# Core48.net
KiCad netlist of a schematic drawn in Altium Designer
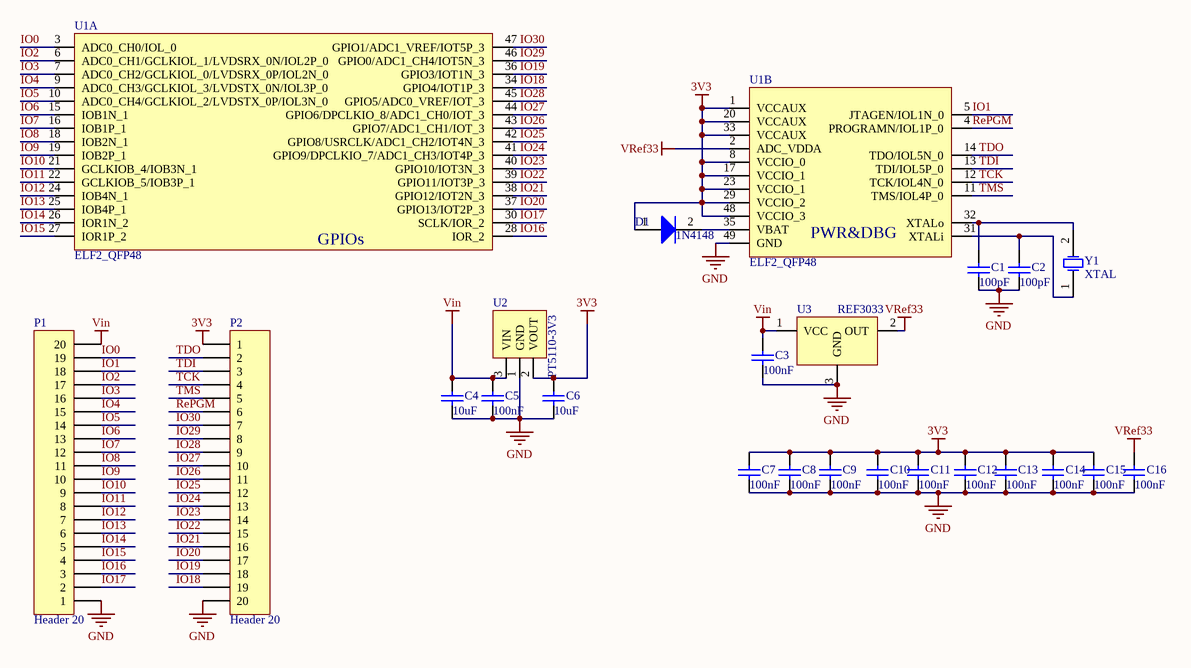
[diagram p0: Core48.SchDoc]

(export (version "E")
  (design (tool "Eeschema 10.0.6"))
  (components
    (comp (ref "C1")
      (value "100pF")
      (footprint "0603C")
      (description "Capacitor")
      (fields (field (name "Comment") "Cap") (field (name "PUBLISHER") "Altium Limited"))
      (libsource (lib "Miscellaneous Devices") (part "Cap"))
    )
    (comp (ref "C2")
      (value "100pF")
      (footprint "0603C")
      (description "Capacitor")
      (fields (field (name "Comment") "Cap") (field (name "PUBLISHER") "Altium Limited"))
      (libsource (lib "Miscellaneous Devices") (part "Cap"))
    )
    (comp (ref "C3")
      (value "100nF")
      (footprint "0603C")
      (description "Capacitor")
      (fields (field (name "Comment") "Cap") (field (name "PUBLISHER") "Altium Limited"))
      (libsource (lib "Miscellaneous Devices") (part "Cap"))
    )
    (comp (ref "C4")
      (value "10uF")
      (footprint "0603C")
      (description "Capacitor")
      (fields (field (name "Comment") "Cap") (field (name "PUBLISHER") "Altium Limited"))
      (libsource (lib "Miscellaneous Devices") (part "Cap"))
    )
    (comp (ref "C5")
      (value "100nF")
      (footprint "0603C")
      (description "Capacitor")
      (fields (field (name "Comment") "Cap") (field (name "PUBLISHER") "Altium Limited"))
      (libsource (lib "Miscellaneous Devices") (part "Cap"))
    )
    (comp (ref "C6")
      (value "10uF")
      (footprint "0603C")
      (description "Capacitor")
      (fields (field (name "Comment") "Cap") (field (name "PUBLISHER") "Altium Limited"))
      (libsource (lib "Miscellaneous Devices") (part "Cap"))
    )
    (comp (ref "C7")
      (value "100nF")
      (footprint "0603C")
      (description "Capacitor")
      (fields (field (name "Comment") "Cap") (field (name "PUBLISHER") "Altium Limited"))
      (libsource (lib "Miscellaneous Devices") (part "Cap"))
    )
    (comp (ref "C8")
      (value "100nF")
      (footprint "0603C")
      (description "Capacitor")
      (fields (field (name "Comment") "Cap") (field (name "PUBLISHER") "Altium Limited"))
      (libsource (lib "Miscellaneous Devices") (part "Cap"))
    )
    (comp (ref "C9")
      (value "100nF")
      (footprint "0603C")
      (description "Capacitor")
      (fields (field (name "Comment") "Cap") (field (name "PUBLISHER") "Altium Limited"))
      (libsource (lib "Miscellaneous Devices") (part "Cap"))
    )
    (comp (ref "C10")
      (value "100nF")
      (footprint "0603C")
      (description "Capacitor")
      (fields (field (name "Comment") "Cap") (field (name "PUBLISHER") "Altium Limited"))
      (libsource (lib "Miscellaneous Devices") (part "Cap"))
    )
    (comp (ref "C11")
      (value "100nF")
      (footprint "0603C")
      (description "Capacitor")
      (fields (field (name "Comment") "Cap") (field (name "PUBLISHER") "Altium Limited"))
      (libsource (lib "Miscellaneous Devices") (part "Cap"))
    )
    (comp (ref "C12")
      (value "100nF")
      (footprint "0603C")
      (description "Capacitor")
      (fields (field (name "Comment") "Cap") (field (name "PUBLISHER") "Altium Limited"))
      (libsource (lib "Miscellaneous Devices") (part "Cap"))
    )
    (comp (ref "C13")
      (value "100nF")
      (footprint "0603C")
      (description "Capacitor")
      (fields (field (name "Comment") "Cap") (field (name "PUBLISHER") "Altium Limited"))
      (libsource (lib "Miscellaneous Devices") (part "Cap"))
    )
    (comp (ref "C14")
      (value "100nF")
      (footprint "0603C")
      (description "Capacitor")
      (fields (field (name "Comment") "Cap") (field (name "PUBLISHER") "Altium Limited"))
      (libsource (lib "Miscellaneous Devices") (part "Cap"))
    )
    (comp (ref "C15")
      (value "100nF")
      (footprint "0603C")
      (description "Capacitor")
      (fields (field (name "Comment") "Cap") (field (name "PUBLISHER") "Altium Limited"))
      (libsource (lib "Miscellaneous Devices") (part "Cap"))
    )
    (comp (ref "C16")
      (value "100nF")
      (footprint "0603C")
      (description "Capacitor")
      (fields (field (name "Comment") "Cap") (field (name "PUBLISHER") "Altium Limited"))
      (libsource (lib "Miscellaneous Devices") (part "Cap"))
    )
    (comp (ref "D1")
      (value "1N4148")
      (footprint "6-0805_Diode")
      (description "Default Diode")
      (fields (field (name "PUBLISHER") "Altium Limited"))
      (libsource (lib "Miscellaneous Devices") (part "Diode"))
    )
    (comp (ref "P1")
      (value "Header 20")
      (footprint "HDR1X20")
      (description "Header, 20-Pin")
      (fields (field (name "PUBLISHER") "Altium Limited"))
      (libsource (lib "Miscellaneous Connectors") (part "Header 20"))
    )
    (comp (ref "P2")
      (value "Header 20")
      (footprint "HDR1X20")
      (description "Header, 20-Pin")
      (fields (field (name "PUBLISHER") "Altium Limited"))
      (libsource (lib "") (part "Header 20_1"))
    )
    (comp (ref "U1")
      (value "ELF2_QFP48")
      (footprint "TSQFP48-7*7")
      (libsource (lib "AnLogic_FPGAs") (part "ELF2_QFP48"))
    )
    (comp (ref "U2")
      (value "PT5110-3V3")
      (footprint "SOT-89-3")
      (libsource (lib "PowerChips") (part "PT5110"))
    )
    (comp (ref "U3") (value "REF3033") (footprint "SOT23") (libsource (lib "PublicSch") (part "REF30xx")))
    (comp (ref "Y1")
      (value "XTAL")
      (footprint "XTAL-5032")
      (description "Crystal Oscillator")
      (fields (field (name "PUBLISHER") "Altium Limited"))
      (libsource (lib "Miscellaneous Devices") (part "XTAL"))
    )
  )
  (nets
    (net (code "1") (name "/IO0") (class "Default")
      (node (ref "P1") (pin "19") (pinfunction "19_19") (pintype "passive"))
      (node (ref "U1") (pin "3") (pinfunction "ADC0_CH0/IOL_0_3") (pintype "power_in"))
    )
    (net (code "2") (name "/IO1") (class "Default")
      (node (ref "P1") (pin "18") (pinfunction "18_18") (pintype "passive"))
      (node (ref "U1") (pin "5") (pinfunction "JTAGEN/IOL1N_0_5") (pintype "power_in"))
    )
    (net (code "3") (name "/IO2") (class "Default")
      (node (ref "P1") (pin "17") (pinfunction "17_17") (pintype "passive"))
      (node (ref "U1") (pin "6") (pinfunction "ADC0_CH1/GCLKIOL_1/LVDSRX_0N/IOL2P_0_6") (pintype "power_in"))
    )
    (net (code "4") (name "/IO3") (class "Default")
      (node (ref "P1") (pin "16") (pinfunction "16_16") (pintype "passive"))
      (node (ref "U1") (pin "7") (pinfunction "ADC0_CH2/GCLKIOL_0/LVDSRX_0P/IOL2N_0_7") (pintype "power_in"))
    )
    (net (code "5") (name "/IO4") (class "Default")
      (node (ref "P1") (pin "15") (pinfunction "15_15") (pintype "passive"))
      (node (ref "U1") (pin "9") (pinfunction "ADC0_CH3/GCLKIOL_3/LVDSTX_0N/IOL3P_0_9") (pintype "power_in"))
    )
    (net (code "6") (name "/IO5") (class "Default")
      (node (ref "P1") (pin "14") (pinfunction "14_14") (pintype "passive"))
      (node (ref "U1") (pin "10") (pinfunction "ADC0_CH4/GCLKIOL_2/LVDSTX_0P/IOL3N_0_10") (pintype "power_in"))
    )
    (net (code "7") (name "/IO6") (class "Default")
      (node (ref "P1") (pin "13") (pinfunction "13_13") (pintype "passive"))
      (node (ref "U1") (pin "15") (pinfunction "IOB1N_1_15") (pintype "power_in"))
    )
    (net (code "8") (name "/IO7") (class "Default")
      (node (ref "P1") (pin "12") (pinfunction "12_12") (pintype "passive"))
      (node (ref "U1") (pin "16") (pinfunction "IOB1P_1_16") (pintype "power_in"))
    )
    (net (code "9") (name "/IO8") (class "Default")
      (node (ref "P1") (pin "11") (pinfunction "11_11") (pintype "passive"))
      (node (ref "U1") (pin "18") (pinfunction "IOB2N_1_18") (pintype "power_in"))
    )
    (net (code "10") (name "/IO9") (class "Default")
      (node (ref "P1") (pin "10") (pinfunction "10_10") (pintype "passive"))
      (node (ref "U1") (pin "19") (pinfunction "IOB2P_1_19") (pintype "power_in"))
    )
    (net (code "11") (name "/IO10") (class "Default")
      (node (ref "P1") (pin "9") (pinfunction "9_9") (pintype "passive"))
      (node (ref "U1") (pin "21") (pinfunction "GCLKIOB_4/IOB3N_1_21") (pintype "power_in"))
    )
    (net (code "12") (name "/IO11") (class "Default")
      (node (ref "P1") (pin "8") (pinfunction "8_8") (pintype "passive"))
      (node (ref "U1") (pin "22") (pinfunction "GCLKIOB_5/IOB3P_1_22") (pintype "power_in"))
    )
    (net (code "13") (name "/IO12") (class "Default")
      (node (ref "P1") (pin "7") (pinfunction "7_7") (pintype "passive"))
      (node (ref "U1") (pin "24") (pinfunction "IOB4N_1_24") (pintype "power_in"))
    )
    (net (code "14") (name "/IO13") (class "Default")
      (node (ref "P1") (pin "6") (pinfunction "6_6") (pintype "passive"))
      (node (ref "U1") (pin "25") (pinfunction "IOB4P_1_25") (pintype "power_in"))
    )
    (net (code "15") (name "/IO14") (class "Default")
      (node (ref "P1") (pin "5") (pinfunction "5_5") (pintype "passive"))
      (node (ref "U1") (pin "26") (pinfunction "IOR1N_2_26") (pintype "power_in"))
    )
    (net (code "16") (name "/IO15") (class "Default")
      (node (ref "P1") (pin "4") (pinfunction "4_4") (pintype "passive"))
      (node (ref "U1") (pin "27") (pinfunction "IOR1P_2_27") (pintype "power_in"))
    )
    (net (code "17") (name "/IO16") (class "Default")
      (node (ref "P1") (pin "3") (pinfunction "3_3") (pintype "passive"))
      (node (ref "U1") (pin "28") (pinfunction "IOR_2_28") (pintype "power_in"))
    )
    (net (code "18") (name "/IO17") (class "Default")
      (node (ref "P1") (pin "2") (pinfunction "2_2") (pintype "passive"))
      (node (ref "U1") (pin "30") (pinfunction "SCLK/IOR_2_30") (pintype "power_in"))
    )
    (net (code "19") (name "/IO18") (class "Default")
      (node (ref "P2") (pin "19") (pinfunction "19_19") (pintype "passive"))
      (node (ref "U1") (pin "34") (pinfunction "GPIO4/IOT1P_3_34") (pintype "power_in"))
    )
    (net (code "20") (name "/IO19") (class "Default")
      (node (ref "P2") (pin "18") (pinfunction "18_18") (pintype "passive"))
      (node (ref "U1") (pin "36") (pinfunction "GPIO3/IOT1N_3_36") (pintype "power_in"))
    )
    (net (code "21") (name "/IO20") (class "Default")
      (node (ref "P2") (pin "17") (pinfunction "17_17") (pintype "passive"))
      (node (ref "U1") (pin "37") (pinfunction "GPIO13/IOT2P_3_37") (pintype "power_in"))
    )
    (net (code "22") (name "/IO21") (class "Default")
      (node (ref "P2") (pin "16") (pinfunction "16_16") (pintype "passive"))
      (node (ref "U1") (pin "38") (pinfunction "GPIO12/IOT2N_3_38") (pintype "power_in"))
    )
    (net (code "23") (name "/IO22") (class "Default")
      (node (ref "P2") (pin "15") (pinfunction "15_15") (pintype "passive"))
      (node (ref "U1") (pin "39") (pinfunction "GPIO11/IOT3P_3_39") (pintype "power_in"))
    )
    (net (code "24") (name "/IO23") (class "Default")
      (node (ref "P2") (pin "14") (pinfunction "14_14") (pintype "passive"))
      (node (ref "U1") (pin "40") (pinfunction "GPIO10/IOT3N_3_40") (pintype "power_in"))
    )
    (net (code "25") (name "/IO24") (class "Default")
      (node (ref "P2") (pin "13") (pinfunction "13_13") (pintype "passive"))
      (node (ref "U1") (pin "41") (pinfunction "GPIO9/DPCLKIO_7/ADC1_CH3/IOT4P_3_41") (pintype "power_in"))
    )
    (net (code "26") (name "/IO25") (class "Default")
      (node (ref "P2") (pin "12") (pinfunction "12_12") (pintype "passive"))
      (node (ref "U1") (pin "42") (pinfunction "GPIO8/USRCLK/ADC1_CH2/IOT4N_3_42") (pintype "power_in"))
    )
    (net (code "27") (name "/IO26") (class "Default")
      (node (ref "P2") (pin "11") (pinfunction "11_11") (pintype "passive"))
      (node (ref "U1") (pin "43") (pinfunction "GPIO7/ADC1_CH1/IOT_3_43") (pintype "power_in"))
    )
    (net (code "28") (name "/IO27") (class "Default")
      (node (ref "P2") (pin "10") (pinfunction "10_10") (pintype "passive"))
      (node (ref "U1") (pin "44") (pinfunction "GPIO6/DPCLKIO_8/ADC1_CH0/IOT_3_44") (pintype "power_in"))
    )
    (net (code "29") (name "/IO28") (class "Default")
      (node (ref "P2") (pin "9") (pinfunction "9_9") (pintype "passive"))
      (node (ref "U1") (pin "45") (pinfunction "GPIO5/ADC0_VREF/IOT_3_45") (pintype "power_in"))
    )
    (net (code "30") (name "/IO29") (class "Default")
      (node (ref "P2") (pin "8") (pinfunction "8_8") (pintype "passive"))
      (node (ref "U1") (pin "46") (pinfunction "GPIO0/ADC1_CH4/IOT5N_3_46") (pintype "power_in"))
    )
    (net (code "31") (name "/IO30") (class "Default")
      (node (ref "P2") (pin "7") (pinfunction "7_7") (pintype "passive"))
      (node (ref "U1") (pin "47") (pinfunction "GPIO1/ADC1_VREF/IOT5P_3_47") (pintype "power_in"))
    )
    (net (code "32") (name "/RePGM") (class "Default")
      (node (ref "P2") (pin "6") (pinfunction "6_6") (pintype "passive"))
      (node (ref "U1") (pin "4") (pinfunction "PROGRAMN/IOL1P_0_4") (pintype "power_in"))
    )
    (net (code "33") (name "/TCK") (class "Default")
      (node (ref "P2") (pin "4") (pinfunction "4_4") (pintype "passive"))
      (node (ref "U1") (pin "12") (pinfunction "TCK/IOL4N_0_12") (pintype "power_in"))
    )
    (net (code "34") (name "/TDI") (class "Default")
      (node (ref "P2") (pin "3") (pinfunction "3_3") (pintype "passive"))
      (node (ref "U1") (pin "13") (pinfunction "TDI/IOL5P_0_13") (pintype "power_in"))
    )
    (net (code "35") (name "/TDO") (class "Default")
      (node (ref "P2") (pin "2") (pinfunction "2_2") (pintype "passive"))
      (node (ref "U1") (pin "14") (pinfunction "TDO/IOL5N_0_14") (pintype "power_in"))
    )
    (net (code "36") (name "/TMS") (class "Default")
      (node (ref "P2") (pin "5") (pinfunction "5_5") (pintype "passive"))
      (node (ref "U1") (pin "11") (pinfunction "TMS/IOL4P_0_11") (pintype "power_in"))
    )
    (net (code "37") (name "3V3") (class "Default")
      (node (ref "C10") (pin "2") (pinfunction "2_2") (pintype "passive"))
      (node (ref "C11") (pin "2") (pinfunction "2_2") (pintype "passive"))
      (node (ref "C12") (pin "2") (pinfunction "2_2") (pintype "passive"))
      (node (ref "C13") (pin "2") (pinfunction "2_2") (pintype "passive"))
      (node (ref "C14") (pin "2") (pinfunction "2_2") (pintype "passive"))
      (node (ref "C15") (pin "2") (pinfunction "2_2") (pintype "passive"))
      (node (ref "C6") (pin "2") (pinfunction "2_2") (pintype "passive"))
      (node (ref "C7") (pin "2") (pinfunction "2_2") (pintype "passive"))
      (node (ref "C8") (pin "2") (pinfunction "2_2") (pintype "passive"))
      (node (ref "C9") (pin "2") (pinfunction "2_2") (pintype "passive"))
      (node (ref "D1") (pin "1") (pinfunction "A_1") (pintype "passive"))
      (node (ref "P2") (pin "1") (pinfunction "1_1") (pintype "passive"))
      (node (ref "U1") (pin "1") (pinfunction "VCCAUX_1") (pintype "power_in"))
      (node (ref "U1") (pin "17") (pinfunction "VCCIO_1_17") (pintype "power_in"))
      (node (ref "U1") (pin "20") (pinfunction "VCCAUX_20") (pintype "power_in"))
      (node (ref "U1") (pin "23") (pinfunction "VCCIO_1_23") (pintype "power_in"))
      (node (ref "U1") (pin "29") (pinfunction "VCCIO_2_29") (pintype "power_in"))
      (node (ref "U1") (pin "33") (pinfunction "VCCAUX_33") (pintype "power_in"))
      (node (ref "U1") (pin "48") (pinfunction "VCCIO_3_48") (pintype "power_in"))
      (node (ref "U1") (pin "8") (pinfunction "VCCIO_0_8") (pintype "power_in"))
      (node (ref "U2") (pin "2") (pinfunction "VOUT_2") (pintype "power_in"))
    )
    (net (code "38") (name "GND") (class "Default")
      (node (ref "C1") (pin "1") (pinfunction "1_1") (pintype "passive"))
      (node (ref "C10") (pin "1") (pinfunction "1_1") (pintype "passive"))
      (node (ref "C11") (pin "1") (pinfunction "1_1") (pintype "passive"))
      (node (ref "C12") (pin "1") (pinfunction "1_1") (pintype "passive"))
      (node (ref "C13") (pin "1") (pinfunction "1_1") (pintype "passive"))
      (node (ref "C14") (pin "1") (pinfunction "1_1") (pintype "passive"))
      (node (ref "C15") (pin "1") (pinfunction "1_1") (pintype "passive"))
      (node (ref "C16") (pin "1") (pinfunction "1_1") (pintype "passive"))
      (node (ref "C2") (pin "1") (pinfunction "1_1") (pintype "passive"))
      (node (ref "C3") (pin "1") (pinfunction "1_1") (pintype "passive"))
      (node (ref "C4") (pin "1") (pinfunction "1_1") (pintype "passive"))
      (node (ref "C5") (pin "1") (pinfunction "1_1") (pintype "passive"))
      (node (ref "C6") (pin "1") (pinfunction "1_1") (pintype "passive"))
      (node (ref "C7") (pin "1") (pinfunction "1_1") (pintype "passive"))
      (node (ref "C8") (pin "1") (pinfunction "1_1") (pintype "passive"))
      (node (ref "C9") (pin "1") (pinfunction "1_1") (pintype "passive"))
      (node (ref "P1") (pin "1") (pinfunction "1_1") (pintype "passive"))
      (node (ref "P2") (pin "20") (pinfunction "20_20") (pintype "passive"))
      (node (ref "U1") (pin "49") (pinfunction "GND_49") (pintype "power_in"))
      (node (ref "U2") (pin "1") (pinfunction "GND_1") (pintype "power_in"))
      (node (ref "U3") (pin "3") (pinfunction "GND_3") (pintype "power_in"))
    )
    (net (code "39") (name "Net-(D1-K)") (class "Default")
      (node (ref "D1") (pin "2") (pinfunction "K_2") (pintype "passive"))
      (node (ref "U1") (pin "35") (pinfunction "VBAT_35") (pintype "power_in"))
    )
    (net (code "40") (name "Net-(U1B-XTALi)") (class "Default")
      (node (ref "C2") (pin "2") (pinfunction "2_2") (pintype "passive"))
      (node (ref "U1") (pin "31") (pinfunction "XTALi_31") (pintype "power_in"))
      (node (ref "Y1") (pin "1") (pinfunction "OSC1_1") (pintype "passive"))
    )
    (net (code "41") (name "Net-(U1B-XTALo)") (class "Default")
      (node (ref "C1") (pin "2") (pinfunction "2_2") (pintype "passive"))
      (node (ref "U1") (pin "32") (pinfunction "XTALo_32") (pintype "power_in"))
      (node (ref "Y1") (pin "2") (pinfunction "OSC2_2") (pintype "passive"))
    )
    (net (code "42") (name "VRef33") (class "Default")
      (node (ref "C16") (pin "2") (pinfunction "2_2") (pintype "passive"))
      (node (ref "U1") (pin "2") (pinfunction "ADC_VDDA_2") (pintype "power_in"))
      (node (ref "U3") (pin "2") (pinfunction "OUT_2") (pintype "power_in"))
    )
    (net (code "43") (name "Vin") (class "Default")
      (node (ref "C3") (pin "2") (pinfunction "2_2") (pintype "passive"))
      (node (ref "C4") (pin "2") (pinfunction "2_2") (pintype "passive"))
      (node (ref "C5") (pin "2") (pinfunction "2_2") (pintype "passive"))
      (node (ref "P1") (pin "20") (pinfunction "20_20") (pintype "passive"))
      (node (ref "U2") (pin "3") (pinfunction "VIN_3") (pintype "power_in"))
      (node (ref "U3") (pin "1") (pinfunction "VCC_1") (pintype "power_in"))
    )
  )
)
